# Main.net
KiCad netlist of a schematic drawn in Altium Designer
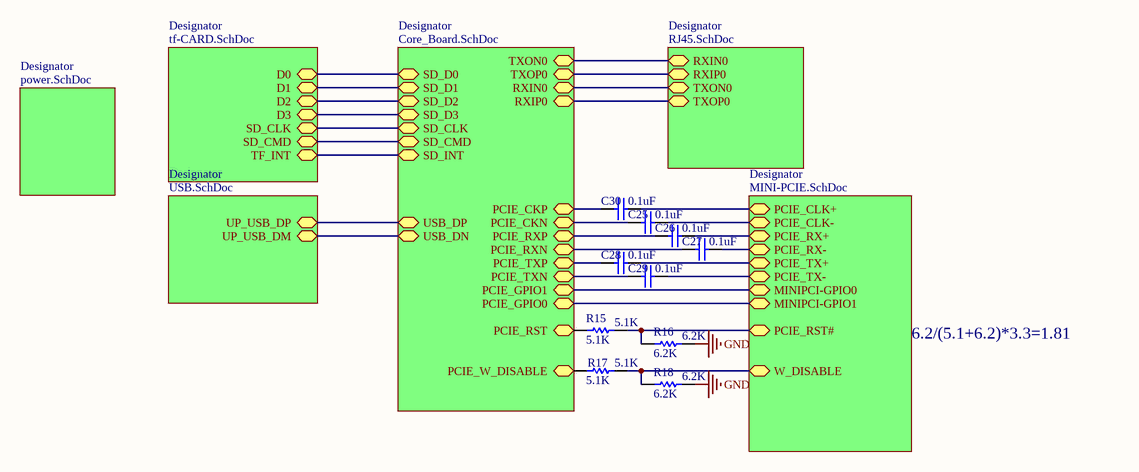
[diagram p0: Main.SchDoc]

(export (version "E")
  (design (tool "Eeschema 10.0.6"))
  (components
    (comp (ref "C25")
      (value "0.1uF")
      (footprint "0402")
      (description "Capacitor")
      (fields (field (name "Comment") "Cap") (field (name "PUBLISHER") "Altium Limited"))
      (libsource (lib "Miscellaneous Devices") (part "Cap"))
    )
    (comp (ref "C26")
      (value "0.1uF")
      (footprint "0402")
      (description "Capacitor")
      (fields (field (name "Comment") "Cap") (field (name "PUBLISHER") "Altium Limited"))
      (libsource (lib "Miscellaneous Devices") (part "Cap"))
    )
    (comp (ref "C27")
      (value "0.1uF")
      (footprint "0402")
      (description "Capacitor")
      (fields (field (name "Comment") "Cap") (field (name "PUBLISHER") "Altium Limited"))
      (libsource (lib "Miscellaneous Devices") (part "Cap"))
    )
    (comp (ref "C28")
      (value "0.1uF")
      (footprint "0402")
      (description "Capacitor")
      (fields (field (name "Comment") "Cap") (field (name "PUBLISHER") "Altium Limited"))
      (libsource (lib "Miscellaneous Devices") (part "Cap"))
    )
    (comp (ref "C29")
      (value "0.1uF")
      (footprint "0402")
      (description "Capacitor")
      (fields (field (name "Comment") "Cap") (field (name "PUBLISHER") "Altium Limited"))
      (libsource (lib "Miscellaneous Devices") (part "Cap"))
    )
    (comp (ref "C30")
      (value "0.1uF")
      (footprint "0402")
      (description "Capacitor")
      (fields (field (name "Comment") "Cap") (field (name "PUBLISHER") "Altium Limited"))
      (libsource (lib "Miscellaneous Devices") (part "Cap"))
    )
    (comp (ref "R15")
      (value "5.1K")
      (footprint "0402")
      (description "Semiconductor Resistor")
      (fields (field (name "ALTIUM_VALUE") "5.1K") (field (name "PUBLISHER") "Altium Limited"))
      (libsource (lib "Miscellaneous Devices") (part "Res Semi"))
    )
    (comp (ref "R16")
      (value "6.2K")
      (footprint "0402")
      (description "Semiconductor Resistor")
      (fields (field (name "ALTIUM_VALUE") "6.2K") (field (name "PUBLISHER") "Altium Limited"))
      (libsource (lib "Miscellaneous Devices") (part "Res Semi"))
    )
    (comp (ref "R17")
      (value "5.1K")
      (footprint "0402")
      (description "Semiconductor Resistor")
      (fields (field (name "ALTIUM_VALUE") "5.1K") (field (name "PUBLISHER") "Altium Limited"))
      (libsource (lib "Miscellaneous Devices") (part "Res Semi"))
    )
    (comp (ref "R18")
      (value "6.2K")
      (footprint "0402")
      (description "Semiconductor Resistor")
      (fields (field (name "ALTIUM_VALUE") "6.2K") (field (name "PUBLISHER") "Altium Limited"))
      (libsource (lib "Miscellaneous Devices") (part "Res Semi"))
    )
  )
  (nets
    (net (code "7") (name "/PCIE_CKN") (class "Default")
      (node (ref "C25") (pin "2") (pinfunction "2_2") (pintype "passive"))
    )
    (net (code "8") (name "/PCIE_CKP") (class "Default")
      (node (ref "C30") (pin "2") (pinfunction "2_2") (pintype "passive"))
    )
    (net (code "9") (name "/PCIE_CLK+") (class "Default")
      (node (ref "C30") (pin "1") (pinfunction "1_1") (pintype "passive"))
    )
    (net (code "10") (name "/PCIE_CLK-") (class "Default")
      (node (ref "C25") (pin "1") (pinfunction "1_1") (pintype "passive"))
    )
    (net (code "11") (name "/PCIE_RST") (class "Default")
      (node (ref "R15") (pin "1") (pinfunction "1_1") (pintype "passive"))
    )
    (net (code "12") (name "/PCIE_RST#") (class "Default")
      (node (ref "R15") (pin "2") (pinfunction "2_2") (pintype "passive"))
      (node (ref "R16") (pin "2") (pinfunction "2_2") (pintype "passive"))
    )
    (net (code "13") (name "/PCIE_RX+") (class "Default")
      (node (ref "C26") (pin "1") (pinfunction "1_1") (pintype "passive"))
    )
    (net (code "14") (name "/PCIE_RX-") (class "Default")
      (node (ref "C27") (pin "1") (pinfunction "1_1") (pintype "passive"))
    )
    (net (code "15") (name "/PCIE_RXN") (class "Default")
      (node (ref "C27") (pin "2") (pinfunction "2_2") (pintype "passive"))
    )
    (net (code "16") (name "/PCIE_RXP") (class "Default")
      (node (ref "C26") (pin "2") (pinfunction "2_2") (pintype "passive"))
    )
    (net (code "17") (name "/PCIE_TX+") (class "Default")
      (node (ref "C28") (pin "1") (pinfunction "1_1") (pintype "passive"))
    )
    (net (code "18") (name "/PCIE_TX-") (class "Default")
      (node (ref "C29") (pin "1") (pinfunction "1_1") (pintype "passive"))
    )
    (net (code "19") (name "/PCIE_TXN") (class "Default")
      (node (ref "C29") (pin "2") (pinfunction "2_2") (pintype "passive"))
    )
    (net (code "20") (name "/PCIE_TXP") (class "Default")
      (node (ref "C28") (pin "2") (pinfunction "2_2") (pintype "passive"))
    )
    (net (code "21") (name "/PCIE_W_DISABLE") (class "Default")
      (node (ref "R17") (pin "1") (pinfunction "1_1") (pintype "passive"))
    )
    (net (code "31") (name "/W_DISABLE") (class "Default")
      (node (ref "R17") (pin "2") (pinfunction "2_2") (pintype "passive"))
      (node (ref "R18") (pin "1") (pinfunction "1_1") (pintype "passive"))
    )
    (net (code "32") (name "GND") (class "Default")
      (node (ref "R16") (pin "1") (pinfunction "1_1") (pintype "passive"))
      (node (ref "R18") (pin "2") (pinfunction "2_2") (pintype "passive"))
    )
  )
)
